# hib_main.net
KiCad netlist of a schematic drawn in EAGLE
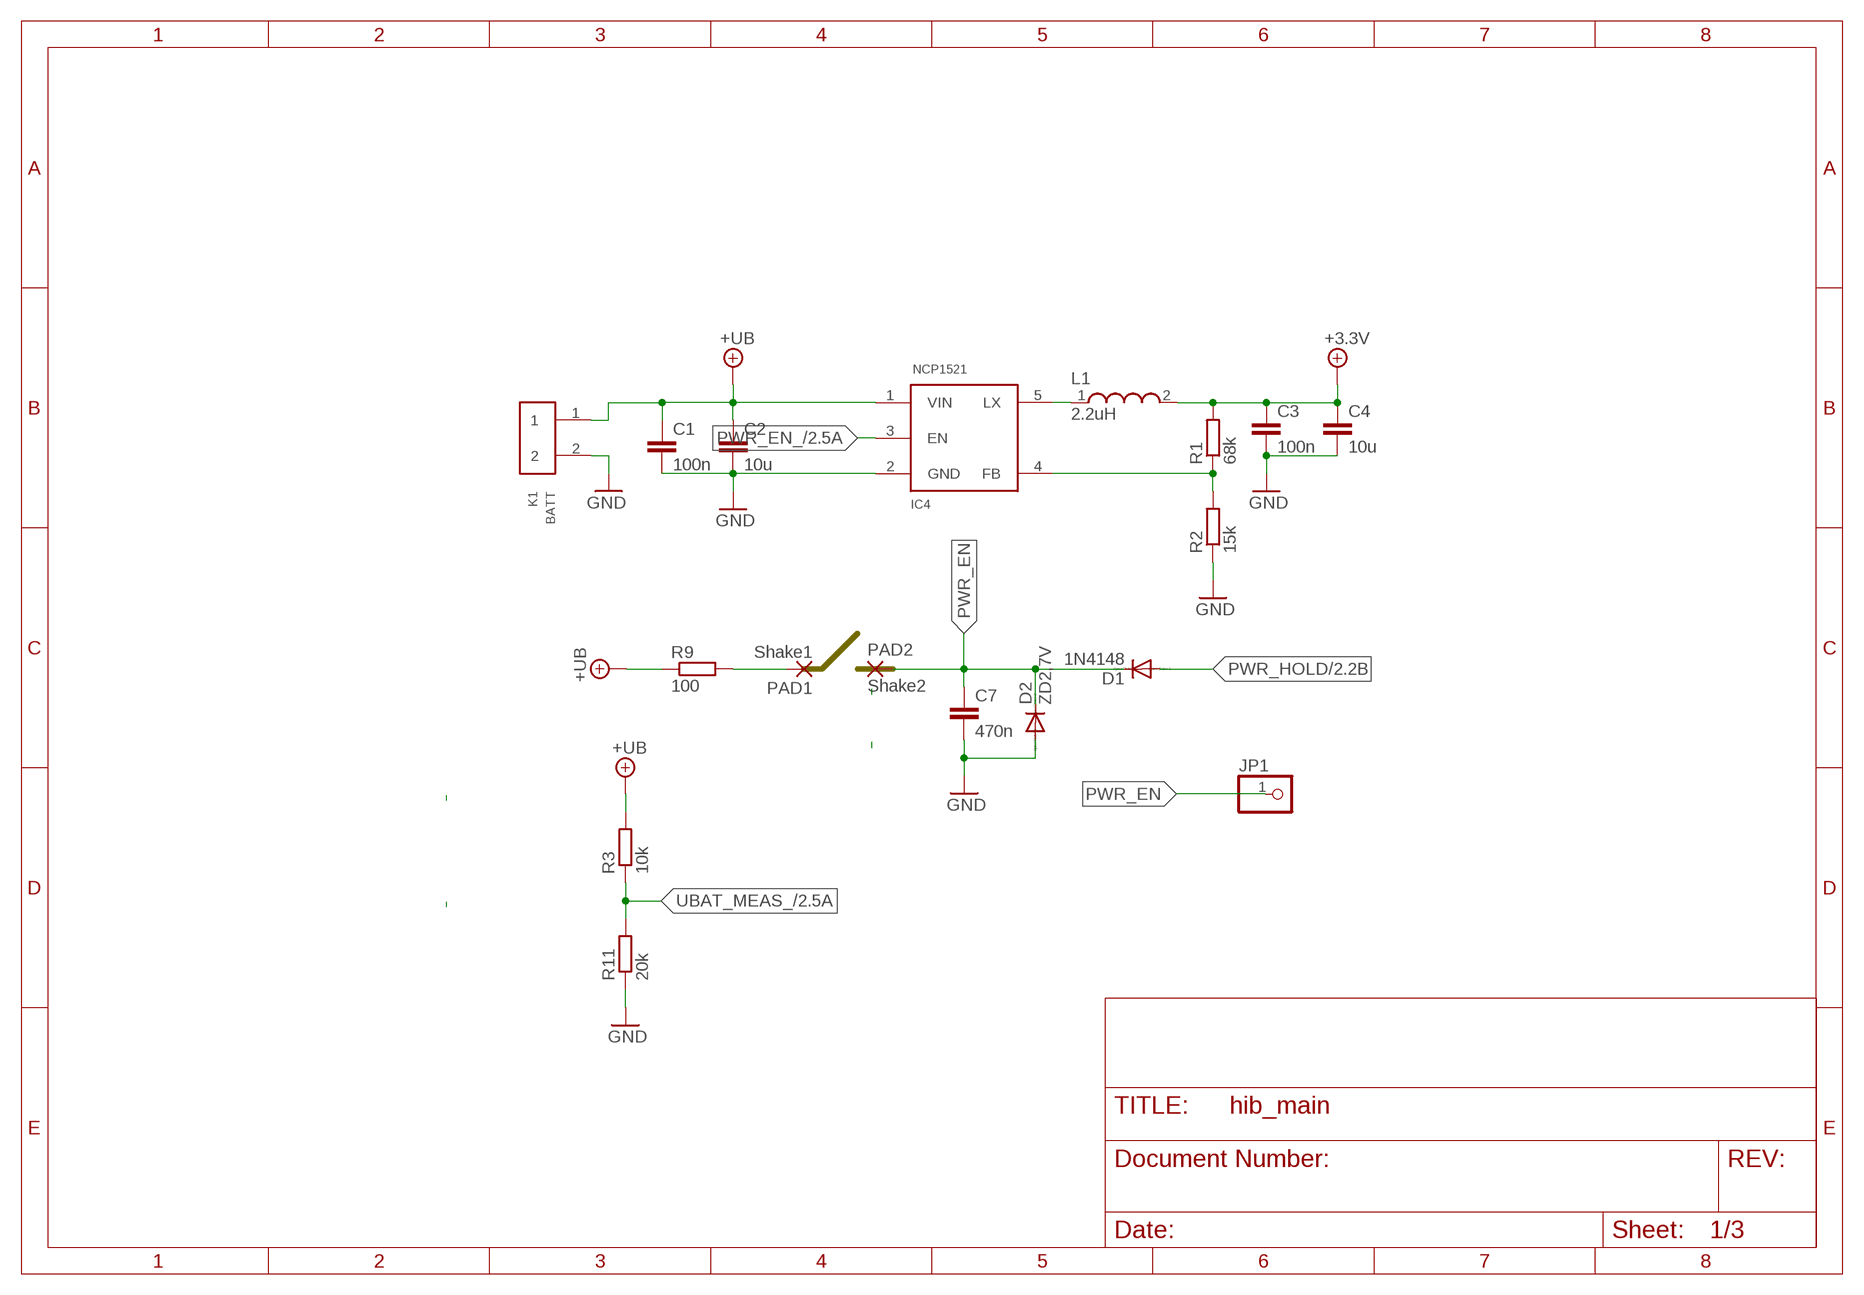
[diagram p0: schematic, sheet 1]
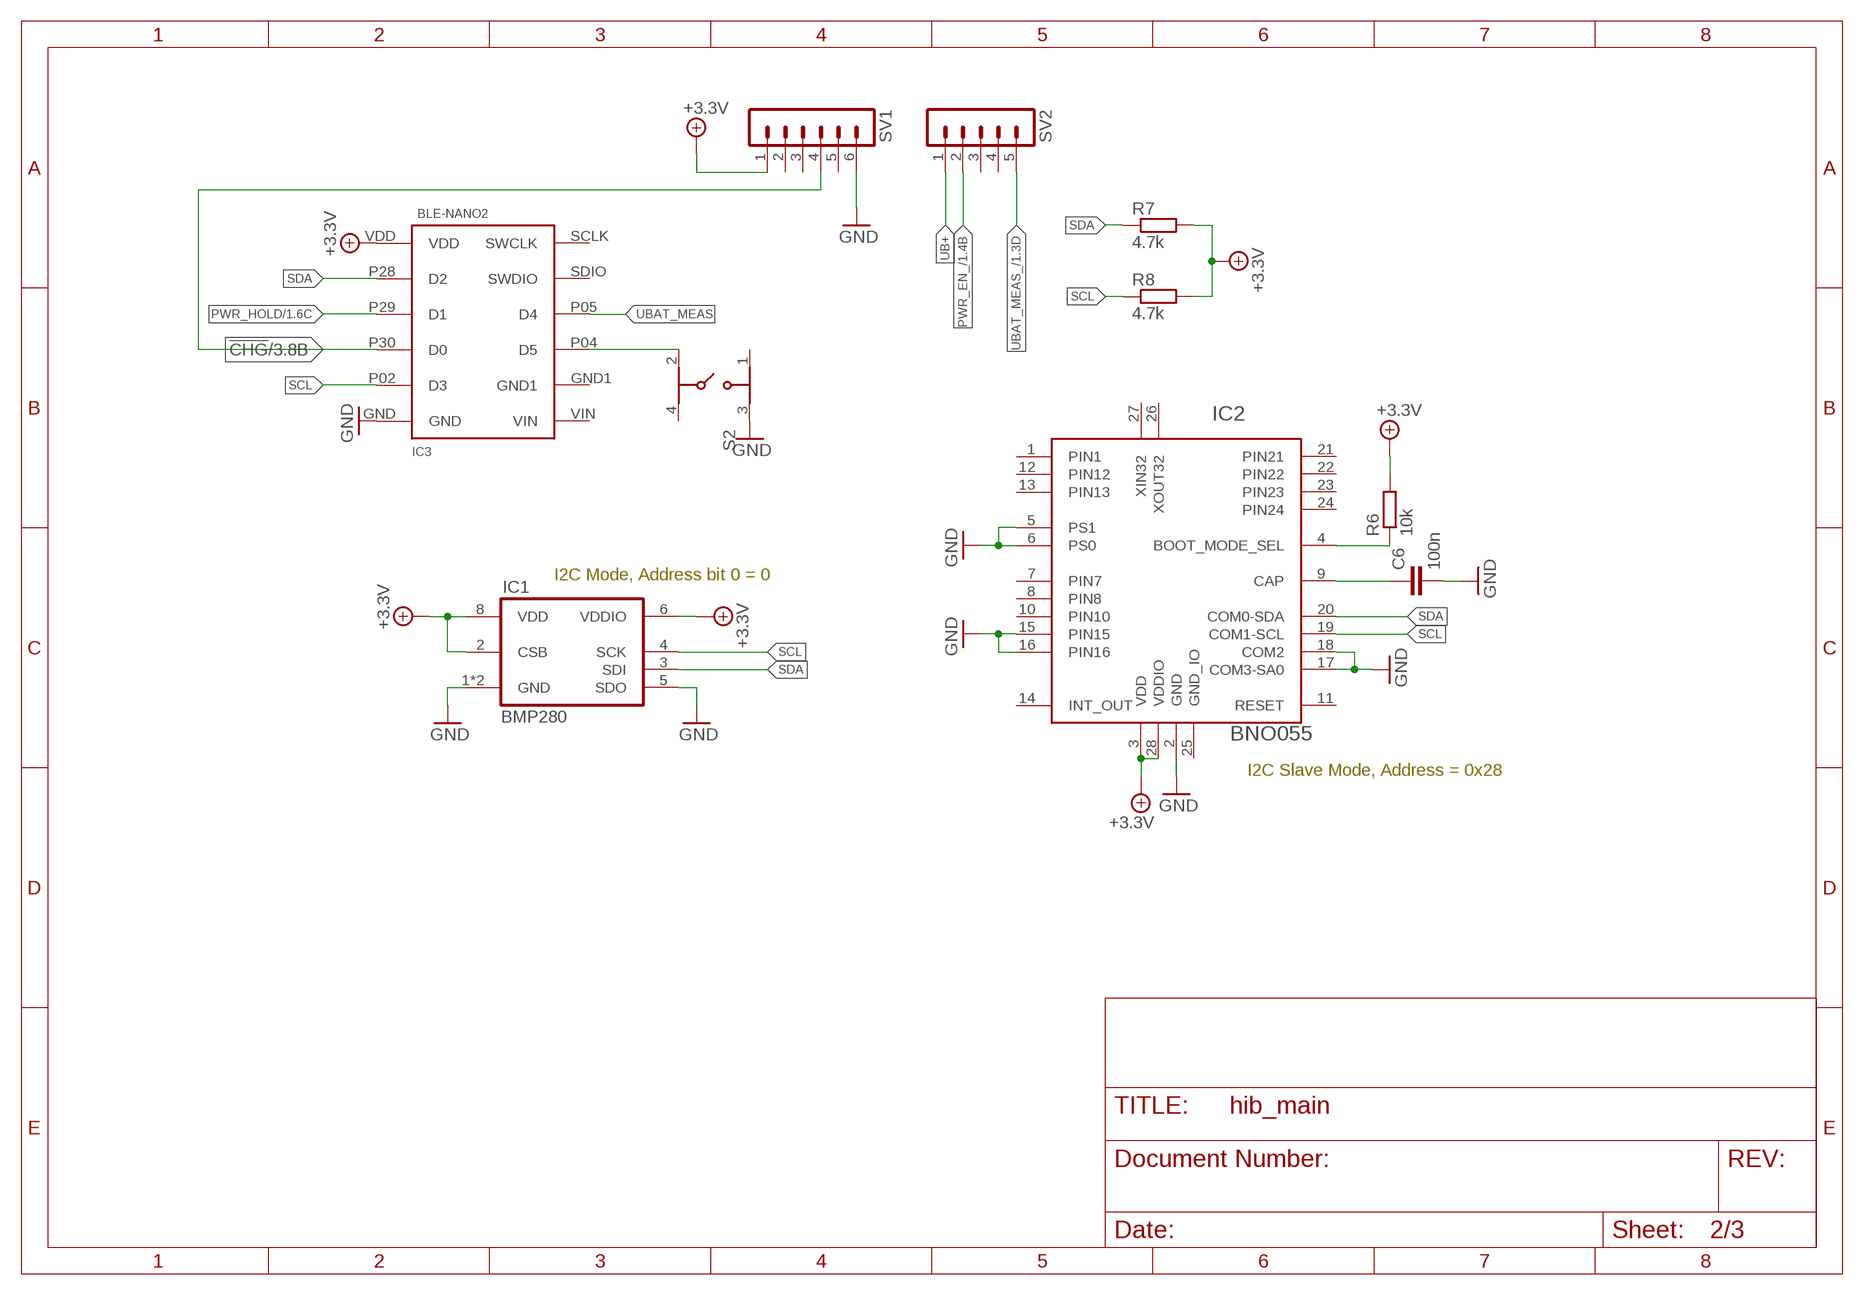
[diagram p1: schematic, sheet 2]
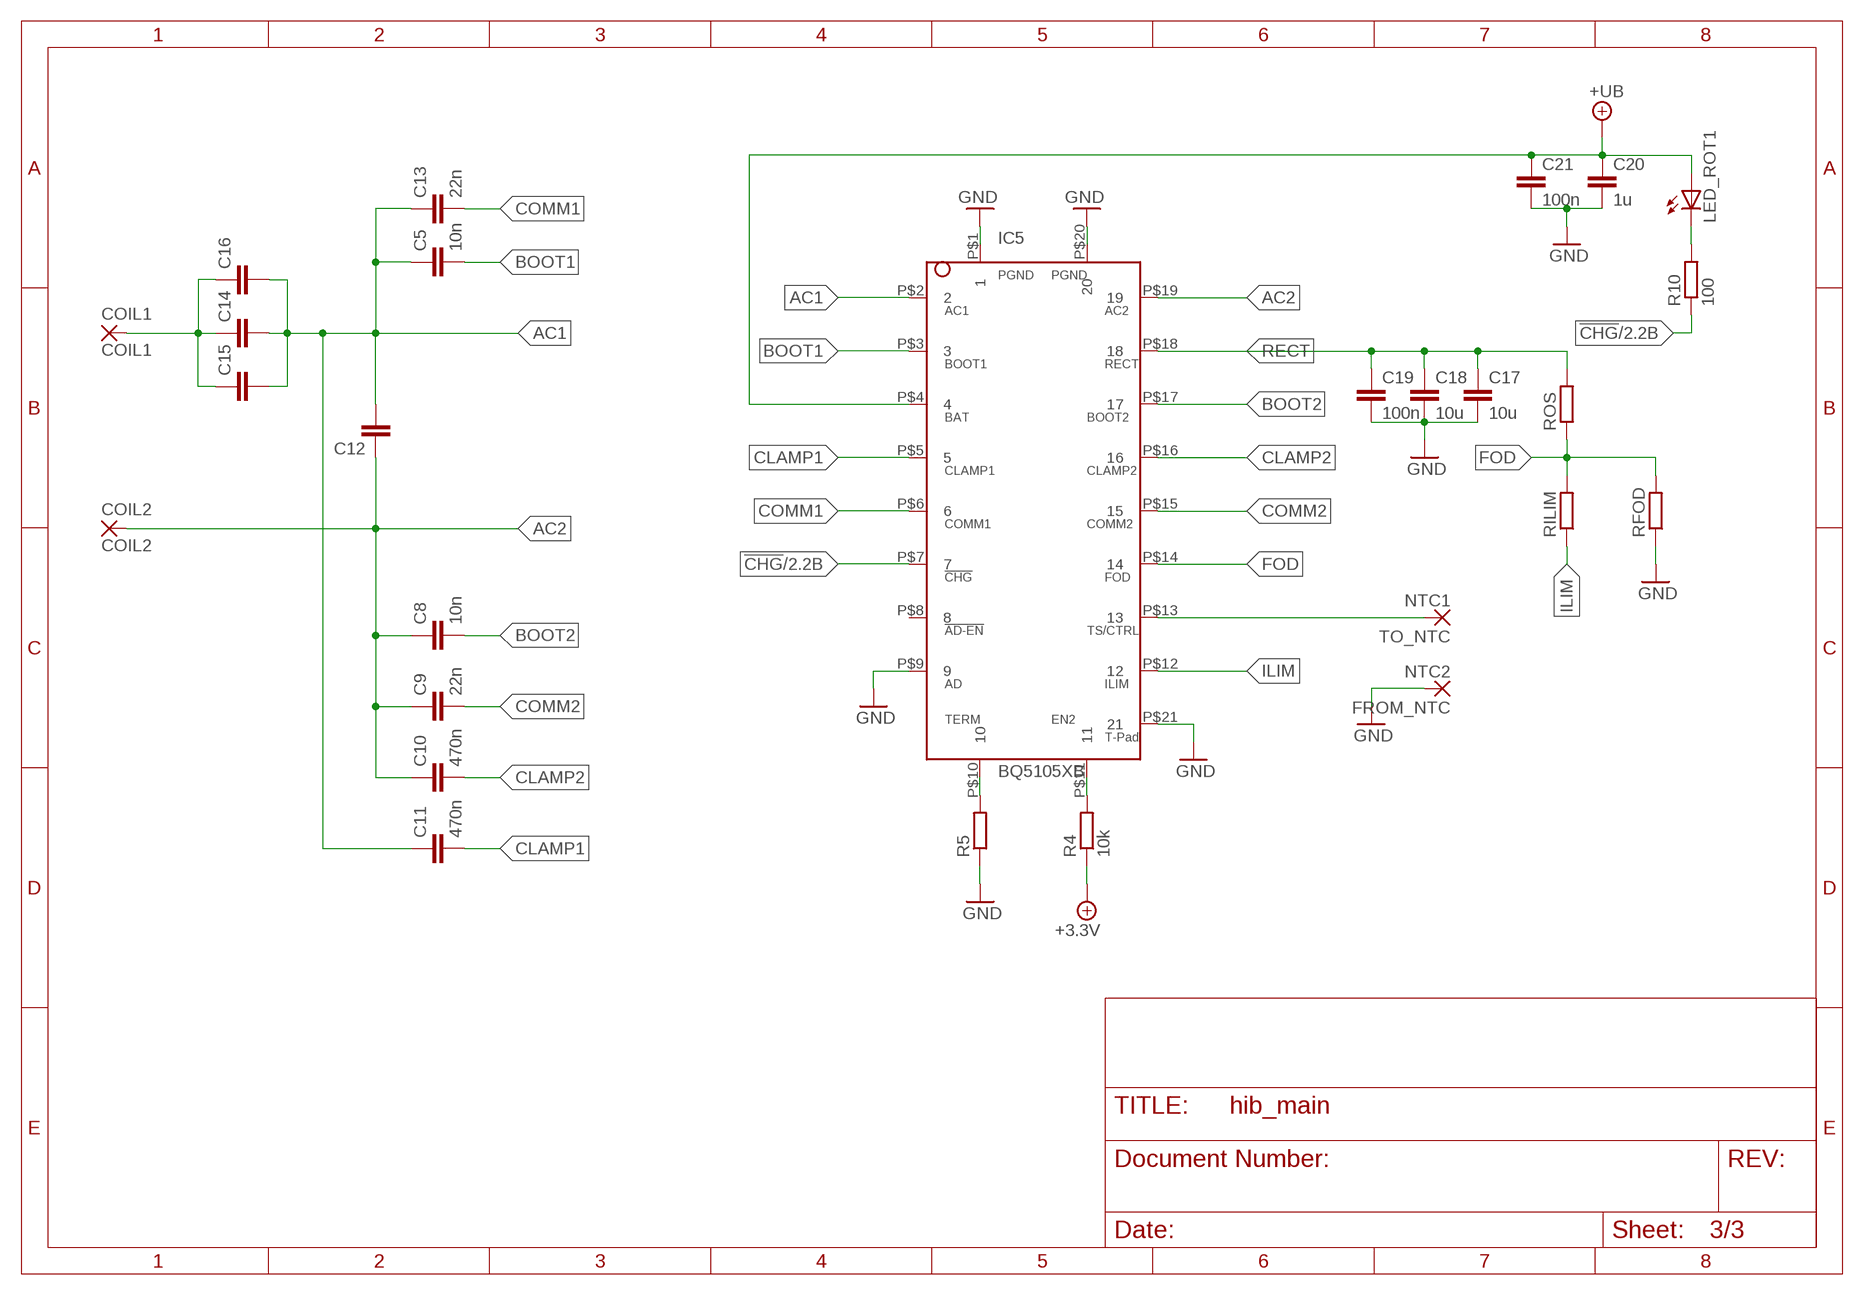
[diagram p2: schematic, sheet 3]

(export (version "E")
  (design (tool "Eeschema 10.0.6"))
  (components
    (comp (ref "C6")
      (value "100n")
      (footprint "eagle-import:C0805M")
      (libsource (lib "eagle-import") (part "C-EUC0805M"))
    )
    (comp (ref "IC1")
      (value "BMP280")
      (footprint "eagle-import:BMP280")
      (libsource (lib "eagle-import") (part "BMP280"))
    )
    (comp (ref "IC2")
      (value "BNO055")
      (footprint "eagle-import:LGA-28_3.80X5.20_0.5")
      (libsource (lib "eagle-import") (part "1658_BNO055"))
    )
    (comp (ref "IC3")
      (value "BLE-NANO2")
      (footprint "eagle-import:BLE-NANO2")
      (libsource (lib "eagle-import") (part "BLE-NANO2"))
    )
    (comp (ref "R6")
      (value "10k")
      (footprint "eagle-import:R0805M")
      (libsource (lib "eagle-import") (part "R-EU_R0805M"))
    )
    (comp (ref "R7")
      (value "4.7k")
      (footprint "eagle-import:R0805M")
      (libsource (lib "eagle-import") (part "R-EU_R0805M"))
    )
    (comp (ref "R8")
      (value "4.7k")
      (footprint "eagle-import:R0805M")
      (libsource (lib "eagle-import") (part "R-EU_R0805M"))
    )
    (comp (ref "S2")
      (value "434153017835")
      (footprint "eagle-import:434153017835")
      (libsource (lib "eagle-import") (part "434153017835"))
    )
    (comp (ref "SV1")
      (value "MA06-1")
      (footprint "eagle-import:MA06-1")
      (libsource (lib "eagle-import") (part "MA06-1"))
    )
    (comp (ref "SV2")
      (value "MA05-1")
      (footprint "eagle-import:MA05-1")
      (libsource (lib "eagle-import") (part "MA05-1"))
    )
    (comp (ref "C1")
      (value "100n")
      (footprint "eagle-import:C0805K")
      (libsource (lib "eagle-import") (part "rcl_334_C-EUC0805K"))
    )
    (comp (ref "C2")
      (value "10u")
      (footprint "eagle-import:C0805K")
      (libsource (lib "eagle-import") (part "rcl_334_C-EUC0805K"))
    )
    (comp (ref "C3")
      (value "100n")
      (footprint "eagle-import:C0805M")
      (libsource (lib "eagle-import") (part "C-EUC0805M"))
    )
    (comp (ref "C4")
      (value "10u")
      (footprint "eagle-import:C0805M")
      (libsource (lib "eagle-import") (part "C-EUC0805M"))
    )
    (comp (ref "C7")
      (value "470n")
      (footprint "eagle-import:C0805M")
      (libsource (lib "eagle-import") (part "C-EUC0805M"))
    )
    (comp (ref "D1")
      (value "1N4148")
      (footprint "eagle-import:MINIMELF")
      (libsource (lib "eagle-import") (part "DIODE-MINIMELF"))
    )
    (comp (ref "D2")
      (value "ZD2,7V")
      (footprint "eagle-import:MINIMELF")
      (libsource (lib "eagle-import") (part "DIODE-MINIMELF"))
    )
    (comp (ref "IC4")
      (value "NCP1521")
      (footprint "eagle-import:SOT23-5L")
      (libsource (lib "eagle-import") (part "NCP1521"))
    )
    (comp (ref "JP1")
      (value "PINHD-1X1")
      (footprint "eagle-import:1X01")
      (libsource (lib "eagle-import") (part "PINHD-1X1"))
    )
    (comp (ref "K1")
      (value "BATT")
      (footprint "eagle-import:620102131822")
      (libsource (lib "eagle-import") (part "620102131822"))
    )
    (comp (ref "L1")
      (value "2.2uH")
      (footprint "eagle-import:WE-MPSB_0805(W=4.0)")
      (libsource (lib "eagle-import") (part "WE-MPSB_0805(HC)"))
    )
    (comp (ref "PAD1")
      (value "Shake1")
      (footprint "eagle-import:SMD1,27-2,54")
      (libsource (lib "eagle-import") (part "WIREPADSMD1,27-254"))
    )
    (comp (ref "PAD2")
      (value "Shake2")
      (footprint "eagle-import:SMD1,27-2,54")
      (libsource (lib "eagle-import") (part "WIREPADSMD1,27-254"))
    )
    (comp (ref "R1")
      (value "68k")
      (footprint "eagle-import:R0603")
      (libsource (lib "eagle-import") (part "R-EU_R0603"))
    )
    (comp (ref "R2")
      (value "15k")
      (footprint "eagle-import:R0603")
      (libsource (lib "eagle-import") (part "R-EU_R0603"))
    )
    (comp (ref "R3")
      (value "10k")
      (footprint "eagle-import:R0603")
      (libsource (lib "eagle-import") (part "R-EU_R0603"))
    )
    (comp (ref "R9")
      (value "100")
      (footprint "eagle-import:R0603")
      (libsource (lib "eagle-import") (part "R-EU_R0603"))
    )
    (comp (ref "R11")
      (value "20k")
      (footprint "eagle-import:R0603")
      (libsource (lib "eagle-import") (part "R-EU_R0603"))
    )
    (comp (ref "C5")
      (value "10n")
      (footprint "eagle-import:C0603K")
      (libsource (lib "eagle-import") (part "rcl_334_C-EUC0603K"))
    )
    (comp (ref "C8")
      (value "10n")
      (footprint "eagle-import:C0603K")
      (libsource (lib "eagle-import") (part "rcl_334_C-EUC0603K"))
    )
    (comp (ref "C9")
      (value "22n")
      (footprint "eagle-import:C0603K")
      (libsource (lib "eagle-import") (part "rcl_334_C-EUC0603K"))
    )
    (comp (ref "C10")
      (value "470n")
      (footprint "eagle-import:C0603K")
      (libsource (lib "eagle-import") (part "rcl_334_C-EUC0603K"))
    )
    (comp (ref "C11")
      (value "470n")
      (footprint "eagle-import:C0603K")
      (libsource (lib "eagle-import") (part "rcl_334_C-EUC0603K"))
    )
    (comp (ref "C12")
      (value "C-EUC0603K")
      (footprint "eagle-import:C0603K")
      (libsource (lib "eagle-import") (part "rcl_334_C-EUC0603K"))
    )
    (comp (ref "C13")
      (value "22n")
      (footprint "eagle-import:C0603K")
      (libsource (lib "eagle-import") (part "rcl_334_C-EUC0603K"))
    )
    (comp (ref "C14")
      (value "C-EUC0603K")
      (footprint "eagle-import:C0603K")
      (libsource (lib "eagle-import") (part "rcl_334_C-EUC0603K"))
    )
    (comp (ref "C15")
      (value "C-EUC0603K")
      (footprint "eagle-import:C0603K")
      (libsource (lib "eagle-import") (part "rcl_334_C-EUC0603K"))
    )
    (comp (ref "C16")
      (value "C-EUC0603K")
      (footprint "eagle-import:C0603K")
      (libsource (lib "eagle-import") (part "rcl_334_C-EUC0603K"))
    )
    (comp (ref "C17")
      (value "10u")
      (footprint "eagle-import:C0603K")
      (libsource (lib "eagle-import") (part "rcl_334_C-EUC0603K"))
    )
    (comp (ref "C18")
      (value "10u")
      (footprint "eagle-import:C0603K")
      (libsource (lib "eagle-import") (part "rcl_334_C-EUC0603K"))
    )
    (comp (ref "C19")
      (value "100n")
      (footprint "eagle-import:C0603K")
      (libsource (lib "eagle-import") (part "rcl_334_C-EUC0603K"))
    )
    (comp (ref "C20")
      (value "1u")
      (footprint "eagle-import:C0603K")
      (libsource (lib "eagle-import") (part "rcl_334_C-EUC0603K"))
    )
    (comp (ref "C21")
      (value "100n")
      (footprint "eagle-import:C0603K")
      (libsource (lib "eagle-import") (part "rcl_334_C-EUC0603K"))
    )
    (comp (ref "COIL1")
      (value "COIL1")
      (footprint "eagle-import:SMD1,27-2,54")
      (libsource (lib "eagle-import") (part "wirepad_412_WIREPADSMD1,27-254"))
    )
    (comp (ref "COIL2")
      (value "COIL2")
      (footprint "eagle-import:SMD1,27-2,54")
      (libsource (lib "eagle-import") (part "wirepad_412_WIREPADSMD1,27-254"))
    )
    (comp (ref "FROM_NTC")
      (value "NTC2")
      (footprint "eagle-import:SMD1,27-2,54")
      (libsource (lib "eagle-import") (part "wirepad_412_WIREPADSMD1,27-254"))
    )
    (comp (ref "IC5")
      (value "BQ5105XB")
      (footprint "eagle-import:VQFN_BQ5105B")
      (libsource (lib "eagle-import") (part "BQ5105XB"))
    )
    (comp (ref "LED_ROT1")
      (value "LEDCHIP-LED0603")
      (footprint "eagle-import:CHIP-LED0603")
      (libsource (lib "eagle-import") (part "LEDCHIP-LED0603"))
    )
    (comp (ref "R4")
      (value "10k")
      (footprint "eagle-import:R0805")
      (libsource (lib "eagle-import") (part "rcl_334_R-EU_R0805"))
    )
    (comp (ref "R5")
      (value "R-EU_R0603")
      (footprint "eagle-import:R0603")
      (libsource (lib "eagle-import") (part "rcl_334_R-EU_R0603"))
    )
    (comp (ref "R10")
      (value "100")
      (footprint "eagle-import:R0603")
      (libsource (lib "eagle-import") (part "rcl_334_R-EU_R0603"))
    )
    (comp (ref "RFOD")
      (value "R-EU_R0805")
      (footprint "eagle-import:R0805")
      (libsource (lib "eagle-import") (part "rcl_334_R-EU_R0805"))
    )
    (comp (ref "RILIM")
      (value "R-EU_R0805")
      (footprint "eagle-import:R0805")
      (libsource (lib "eagle-import") (part "rcl_334_R-EU_R0805"))
    )
    (comp (ref "ROS")
      (value "R-EU_R0805")
      (footprint "eagle-import:R0805")
      (libsource (lib "eagle-import") (part "rcl_334_R-EU_R0805"))
    )
    (comp (ref "TO_NTC")
      (value "NTC1")
      (footprint "eagle-import:SMD1,27-2,54")
      (libsource (lib "eagle-import") (part "wirepad_412_WIREPADSMD1,27-254"))
    )
  )
  (nets
    (net (code "1") (name "+3,3V") (class "Default")
      (node (ref "C3") (pin "1") (pinfunction "1_1") (pintype "passive"))
      (node (ref "C4") (pin "1") (pinfunction "1_1") (pintype "passive"))
      (node (ref "IC1") (pin "2") (pinfunction "CSB_2") (pintype "input"))
      (node (ref "IC1") (pin "6") (pinfunction "VDDIO_6") (pintype "power_in"))
      (node (ref "IC1") (pin "8") (pinfunction "VDD_8") (pintype "power_in"))
      (node (ref "IC2") (pin "28") (pinfunction "VDDIO_28") (pintype "power_in"))
      (node (ref "IC2") (pin "3") (pinfunction "VDD_3") (pintype "power_in"))
      (node (ref "IC3") (pin "VDD") (pinfunction "VDD_VDD") (pintype "bidirectional"))
      (node (ref "L1") (pin "2") (pinfunction "2_2") (pintype "passive"))
      (node (ref "R1") (pin "2") (pinfunction "2_2") (pintype "passive"))
      (node (ref "R4") (pin "1") (pinfunction "1_1") (pintype "passive"))
      (node (ref "R6") (pin "2") (pinfunction "2_2") (pintype "passive"))
      (node (ref "R7") (pin "2") (pinfunction "2_2") (pintype "passive"))
      (node (ref "R8") (pin "2") (pinfunction "2_2") (pintype "passive"))
      (node (ref "SV1") (pin "1") (pinfunction "1_1") (pintype "passive"))
    )
    (net (code "2") (name "+UB") (class "Default")
      (node (ref "C1") (pin "1") (pinfunction "1_1") (pintype "passive"))
      (node (ref "C2") (pin "1") (pinfunction "1_1") (pintype "passive"))
      (node (ref "C20") (pin "1") (pinfunction "1_1") (pintype "passive"))
      (node (ref "C21") (pin "1") (pinfunction "1_1") (pintype "passive"))
      (node (ref "IC4") (pin "1") (pinfunction "VIN_1") (pintype "bidirectional"))
      (node (ref "IC5") (pin "P$4") (pinfunction "4_P$4") (pintype "bidirectional"))
      (node (ref "K1") (pin "1") (pinfunction "1_1") (pintype "passive"))
      (node (ref "LED_ROT1") (pin "A") (pinfunction "A_A") (pintype "passive"))
      (node (ref "R3") (pin "2") (pinfunction "2_2") (pintype "passive"))
      (node (ref "R9") (pin "1") (pinfunction "1_1") (pintype "passive"))
    )
    (net (code "3") (name "AC1") (class "Default")
      (node (ref "C11") (pin "1") (pinfunction "1_1") (pintype "passive"))
      (node (ref "C12") (pin "2") (pinfunction "2_2") (pintype "passive"))
      (node (ref "C13") (pin "1") (pinfunction "1_1") (pintype "passive"))
      (node (ref "C14") (pin "2") (pinfunction "2_2") (pintype "passive"))
      (node (ref "C15") (pin "2") (pinfunction "2_2") (pintype "passive"))
      (node (ref "C16") (pin "2") (pinfunction "2_2") (pintype "passive"))
      (node (ref "C5") (pin "1") (pinfunction "1_1") (pintype "passive"))
      (node (ref "IC5") (pin "P$2") (pinfunction "2_P$2") (pintype "bidirectional"))
    )
    (net (code "4") (name "AC2") (class "Default")
      (node (ref "C10") (pin "1") (pinfunction "1_1") (pintype "passive"))
      (node (ref "C12") (pin "1") (pinfunction "1_1") (pintype "passive"))
      (node (ref "C8") (pin "1") (pinfunction "1_1") (pintype "passive"))
      (node (ref "C9") (pin "1") (pinfunction "1_1") (pintype "passive"))
      (node (ref "COIL2") (pin "1") (pinfunction "P_1") (pintype "passive"))
      (node (ref "IC5") (pin "P$19") (pinfunction "19_P$19") (pintype "bidirectional"))
    )
    (net (code "5") (name "BOOT1") (class "Default")
      (node (ref "C5") (pin "2") (pinfunction "2_2") (pintype "passive"))
      (node (ref "IC5") (pin "P$3") (pinfunction "3_P$3") (pintype "bidirectional"))
    )
    (net (code "6") (name "BOOT2") (class "Default")
      (node (ref "C8") (pin "2") (pinfunction "2_2") (pintype "passive"))
      (node (ref "IC5") (pin "P$17") (pinfunction "17_P$17") (pintype "bidirectional"))
    )
    (net (code "7") (name "CLAMP1") (class "Default")
      (node (ref "C11") (pin "2") (pinfunction "2_2") (pintype "passive"))
      (node (ref "IC5") (pin "P$5") (pinfunction "5_P$5") (pintype "bidirectional"))
    )
    (net (code "8") (name "CLAMP2") (class "Default")
      (node (ref "C10") (pin "2") (pinfunction "2_2") (pintype "passive"))
      (node (ref "IC5") (pin "P$16") (pinfunction "16_P$16") (pintype "bidirectional"))
    )
    (net (code "9") (name "COMM1") (class "Default")
      (node (ref "C13") (pin "2") (pinfunction "2_2") (pintype "passive"))
      (node (ref "IC5") (pin "P$6") (pinfunction "6_P$6") (pintype "bidirectional"))
    )
    (net (code "10") (name "COMM2") (class "Default")
      (node (ref "C9") (pin "2") (pinfunction "2_2") (pintype "passive"))
      (node (ref "IC5") (pin "P$15") (pinfunction "15_P$15") (pintype "bidirectional"))
    )
    (net (code "11") (name "FOD") (class "Default")
      (node (ref "IC5") (pin "P$14") (pinfunction "14_P$14") (pintype "bidirectional"))
      (node (ref "RFOD") (pin "2") (pinfunction "2_2") (pintype "passive"))
      (node (ref "RILIM") (pin "2") (pinfunction "2_2") (pintype "passive"))
      (node (ref "ROS") (pin "1") (pinfunction "1_1") (pintype "passive"))
    )
    (net (code "12") (name "GND") (class "Default")
      (node (ref "C1") (pin "2") (pinfunction "2_2") (pintype "passive"))
      (node (ref "C17") (pin "2") (pinfunction "2_2") (pintype "passive"))
      (node (ref "C18") (pin "2") (pinfunction "2_2") (pintype "passive"))
      (node (ref "C19") (pin "2") (pinfunction "2_2") (pintype "passive"))
      (node (ref "C2") (pin "2") (pinfunction "2_2") (pintype "passive"))
      (node (ref "C20") (pin "2") (pinfunction "2_2") (pintype "passive"))
      (node (ref "C21") (pin "2") (pinfunction "2_2") (pintype "passive"))
      (node (ref "C3") (pin "2") (pinfunction "2_2") (pintype "passive"))
      (node (ref "C4") (pin "2") (pinfunction "2_2") (pintype "passive"))
      (node (ref "C6") (pin "2") (pinfunction "2_2") (pintype "passive"))
      (node (ref "C7") (pin "2") (pinfunction "2_2") (pintype "passive"))
      (node (ref "D2") (pin "A") (pinfunction "A_A") (pintype "passive"))
      (node (ref "FROM_NTC") (pin "1") (pinfunction "P_1") (pintype "passive"))
      (node (ref "IC1") (pin "1") (pinfunction "GND_1") (pintype "power_in"))
      (node (ref "IC1") (pin "5") (pinfunction "SDO_5") (pintype "input"))
      (node (ref "IC1") (pin "7") (pinfunction "GND_7") (pintype "power_in"))
      (node (ref "IC2") (pin "15") (pinfunction "PIN15_15") (pintype "passive"))
      (node (ref "IC2") (pin "16") (pinfunction "PIN16_16") (pintype "passive"))
      (node (ref "IC2") (pin "17") (pinfunction "COM3-SA0_17") (pintype "bidirectional"))
      (node (ref "IC2") (pin "18") (pinfunction "COM2_18") (pintype "bidirectional"))
      (node (ref "IC2") (pin "2") (pinfunction "GND_2") (pintype "power_in"))
      (node (ref "IC2") (pin "5") (pinfunction "PS1_5") (pintype "input"))
      (node (ref "IC2") (pin "6") (pinfunction "PS0_6") (pintype "input"))
      (node (ref "IC3") (pin "GND") (pinfunction "GND_GND") (pintype "bidirectional"))
      (node (ref "IC4") (pin "2") (pinfunction "GND_2") (pintype "bidirectional"))
      (node (ref "IC5") (pin "P$1") (pinfunction "1_P$1") (pintype "bidirectional"))
      (node (ref "IC5") (pin "P$20") (pinfunction "20_P$20") (pintype "bidirectional"))
      (node (ref "IC5") (pin "P$21") (pinfunction "21_P$21") (pintype "bidirectional"))
      (node (ref "IC5") (pin "P$9") (pinfunction "9_P$9") (pintype "bidirectional"))
      (node (ref "K1") (pin "2") (pinfunction "2_2") (pintype "passive"))
      (node (ref "R11") (pin "1") (pinfunction "1_1") (pintype "passive"))
      (node (ref "R2") (pin "1") (pinfunction "1_1") (pintype "passive"))
      (node (ref "R5") (pin "1") (pinfunction "1_1") (pintype "passive"))
      (node (ref "RFOD") (pin "1") (pinfunction "1_1") (pintype "passive"))
      (node (ref "S2") (pin "3") (pinfunction "2_3") (pintype "passive"))
      (node (ref "SV1") (pin "6") (pinfunction "6_6") (pintype "passive"))
    )
    (net (code "13") (name "GND_IO") (class "Default")
      (node (ref "IC2") (pin "25") (pinfunction "GND_IO_25") (pintype "power_in"))
    )
    (net (code "14") (name "ILIM") (class "Default")
      (node (ref "IC5") (pin "P$12") (pinfunction "12_P$12") (pintype "bidirectional"))
      (node (ref "RILIM") (pin "1") (pinfunction "1_1") (pintype "passive"))
    )
    (net (code "15") (name "Net-(COIL1-P)") (class "Default")
      (node (ref "C14") (pin "1") (pinfunction "1_1") (pintype "passive"))
      (node (ref "C15") (pin "1") (pinfunction "1_1") (pintype "passive"))
      (node (ref "C16") (pin "1") (pinfunction "1_1") (pintype "passive"))
      (node (ref "COIL1") (pin "1") (pinfunction "P_1") (pintype "passive"))
    )
    (net (code "16") (name "Net-(IC2-BOOT_MODE_SEL)") (class "Default")
      (node (ref "IC2") (pin "4") (pinfunction "BOOT_MODE_SEL_4") (pintype "input"))
      (node (ref "R6") (pin "1") (pinfunction "1_1") (pintype "passive"))
    )
    (net (code "17") (name "Net-(IC2-CAP)") (class "Default")
      (node (ref "C6") (pin "1") (pinfunction "1_1") (pintype "passive"))
      (node (ref "IC2") (pin "9") (pinfunction "CAP_9") (pintype "tri_state"))
    )
    (net (code "18") (name "Net-(IC3-D5)") (class "Default")
      (node (ref "IC3") (pin "P04") (pinfunction "D5_P04") (pintype "bidirectional"))
      (node (ref "S2") (pin "2") (pinfunction "3_2") (pintype "passive"))
    )
    (net (code "19") (name "Net-(IC4-FB)") (class "Default")
      (node (ref "IC4") (pin "4") (pinfunction "FB_4") (pintype "bidirectional"))
      (node (ref "R1") (pin "1") (pinfunction "1_1") (pintype "passive"))
      (node (ref "R2") (pin "2") (pinfunction "2_2") (pintype "passive"))
    )
    (net (code "20") (name "Net-(IC4-LX)") (class "Default")
      (node (ref "IC4") (pin "5") (pinfunction "LX_5") (pintype "bidirectional"))
      (node (ref "L1") (pin "1") (pinfunction "1_1") (pintype "passive"))
    )
    (net (code "21") (name "Net-(IC5-10)") (class "Default")
      (node (ref "IC5") (pin "P$10") (pinfunction "10_P$10") (pintype "bidirectional"))
      (node (ref "R5") (pin "2") (pinfunction "2_2") (pintype "passive"))
    )
    (net (code "22") (name "Net-(IC5-11)") (class "Default")
      (node (ref "IC5") (pin "P$11") (pinfunction "11_P$11") (pintype "bidirectional"))
      (node (ref "R4") (pin "2") (pinfunction "2_2") (pintype "passive"))
    )
    (net (code "23") (name "Net-(IC5-13)") (class "Default")
      (node (ref "IC5") (pin "P$13") (pinfunction "13_P$13") (pintype "bidirectional"))
      (node (ref "TO_NTC") (pin "1") (pinfunction "P_1") (pintype "passive"))
    )
    (net (code "24") (name "Net-(LED_ROT1-PadC)") (class "Default")
      (node (ref "LED_ROT1") (pin "C") (pinfunction "C_C") (pintype "passive"))
      (node (ref "R10") (pin "2") (pinfunction "2_2") (pintype "passive"))
    )
    (net (code "25") (name "Net-(PAD1-P)") (class "Default")
      (node (ref "PAD1") (pin "1") (pinfunction "P_1") (pintype "passive"))
      (node (ref "R9") (pin "2") (pinfunction "2_2") (pintype "passive"))
    )
    (net (code "26") (name "PWR_EN") (class "Default")
      (node (ref "C7") (pin "1") (pinfunction "1_1") (pintype "passive"))
      (node (ref "D1") (pin "C") (pinfunction "C_C") (pintype "passive"))
      (node (ref "D2") (pin "C") (pinfunction "C_C") (pintype "passive"))
      (node (ref "JP1") (pin "1") (pinfunction "1_1") (pintype "passive"))
      (node (ref "PAD2") (pin "1") (pinfunction "P_1") (pintype "passive"))
    )
    (net (code "27") (name "PWR_EN_") (class "Default")
      (node (ref "IC4") (pin "3") (pinfunction "EN_3") (pintype "bidirectional"))
      (node (ref "SV2") (pin "2") (pinfunction "2_2") (pintype "passive"))
    )
    (net (code "28") (name "PWR_HOLD") (class "Default")
      (node (ref "D1") (pin "A") (pinfunction "A_A") (pintype "passive"))
      (node (ref "IC3") (pin "P29") (pinfunction "D1_P29") (pintype "bidirectional"))
    )
    (net (code "29") (name "RECT") (class "Default")
      (node (ref "C17") (pin "1") (pinfunction "1_1") (pintype "passive"))
      (node (ref "C18") (pin "1") (pinfunction "1_1") (pintype "passive"))
      (node (ref "C19") (pin "1") (pinfunction "1_1") (pintype "passive"))
      (node (ref "IC5") (pin "P$18") (pinfunction "18_P$18") (pintype "bidirectional"))
      (node (ref "ROS") (pin "2") (pinfunction "2_2") (pintype "passive"))
    )
    (net (code "30") (name "SCL") (class "Default")
      (node (ref "IC1") (pin "4") (pinfunction "SCK_4") (pintype "bidirectional"))
      (node (ref "IC2") (pin "19") (pinfunction "COM1-SCL_19") (pintype "bidirectional"))
      (node (ref "IC3") (pin "P02") (pinfunction "D3_P02") (pintype "bidirectional"))
      (node (ref "R8") (pin "1") (pinfunction "1_1") (pintype "passive"))
    )
    (net (code "31") (name "SDA") (class "Default")
      (node (ref "IC1") (pin "3") (pinfunction "SDI_3") (pintype "bidirectional"))
      (node (ref "IC2") (pin "20") (pinfunction "COM0-SDA_20") (pintype "bidirectional"))
      (node (ref "IC3") (pin "P28") (pinfunction "D2_P28") (pintype "bidirectional"))
      (node (ref "R7") (pin "1") (pinfunction "1_1") (pintype "passive"))
    )
    (net (code "32") (name "UB+") (class "Default")
      (node (ref "SV2") (pin "1") (pinfunction "1_1") (pintype "passive"))
    )
    (net (code "33") (name "UBAT_MEAS") (class "Default")
      (node (ref "IC3") (pin "P05") (pinfunction "D4_P05") (pintype "bidirectional"))
    )
    (net (code "34") (name "UBAT_MEAS_") (class "Default")
      (node (ref "R11") (pin "2") (pinfunction "2_2") (pintype "passive"))
      (node (ref "R3") (pin "1") (pinfunction "1_1") (pintype "passive"))
      (node (ref "SV2") (pin "5") (pinfunction "5_5") (pintype "passive"))
    )
    (net (code "35") (name "unconnected-(IC2-INT_OUT-Pad14)") (class "Default")
      (node (ref "IC2") (pin "14") (pinfunction "INT_OUT_14") (pintype "output"))
    )
    (net (code "36") (name "unconnected-(IC2-PIN1-Pad1)") (class "Default")
      (node (ref "IC2") (pin "1") (pinfunction "PIN1_1") (pintype "no_connect"))
    )
    (net (code "37") (name "unconnected-(IC2-PIN7-Pad7)") (class "Default")
      (node (ref "IC2") (pin "7") (pinfunction "PIN7_7") (pintype "tri_state"))
    )
    (net (code "38") (name "unconnected-(IC2-PIN8-Pad8)") (class "Default")
      (node (ref "IC2") (pin "8") (pinfunction "PIN8_8") (pintype "tri_state"))
    )
    (net (code "39") (name "unconnected-(IC2-PIN10-Pad10)") (class "Default")
      (node (ref "IC2") (pin "10") (pinfunction "PIN10_10") (pintype "passive"))
    )
    (net (code "40") (name "unconnected-(IC2-PIN12-Pad12)") (class "Default")
      (node (ref "IC2") (pin "12") (pinfunction "PIN12_12") (pintype "passive"))
    )
    (net (code "41") (name "unconnected-(IC2-PIN13-Pad13)") (class "Default")
      (node (ref "IC2") (pin "13") (pinfunction "PIN13_13") (pintype "passive"))
    )
    (net (code "42") (name "unconnected-(IC2-PIN21-Pad21)") (class "Default")
      (node (ref "IC2") (pin "21") (pinfunction "PIN21_21") (pintype "passive"))
    )
    (net (code "43") (name "unconnected-(IC2-PIN22-Pad22)") (class "Default")
      (node (ref "IC2") (pin "22") (pinfunction "PIN22_22") (pintype "passive"))
    )
    (net (code "44") (name "unconnected-(IC2-PIN23-Pad23)") (class "Default")
      (node (ref "IC2") (pin "23") (pinfunction "PIN23_23") (pintype "passive"))
    )
    (net (code "45") (name "unconnected-(IC2-PIN24-Pad24)") (class "Default")
      (node (ref "IC2") (pin "24") (pinfunction "PIN24_24") (pintype "passive"))
    )
    (net (code "46") (name "unconnected-(IC2-RESET-Pad11)") (class "Default")
      (node (ref "IC2") (pin "11") (pinfunction "RESET_11") (pintype "input"))
    )
    (net (code "47") (name "unconnected-(IC2-XIN32-Pad27)") (class "Default")
      (node (ref "IC2") (pin "27") (pinfunction "XIN32_27") (pintype "bidirectional"))
    )
    (net (code "48") (name "unconnected-(IC2-XOUT32-Pad26)") (class "Default")
      (node (ref "IC2") (pin "26") (pinfunction "XOUT32_26") (pintype "output"))
    )
    (net (code "49") (name "unconnected-(IC3-PadGND1)") (class "Default")
      (node (ref "IC3") (pin "GND1") (pinfunction "GND1_GND1") (pintype "bidirectional"))
    )
    (net (code "50") (name "unconnected-(IC3-PadVIN)") (class "Default")
      (node (ref "IC3") (pin "VIN") (pinfunction "VIN_VIN") (pintype "bidirectional"))
    )
    (net (code "51") (name "unconnected-(IC3-SWCLK-PadSCLK)") (class "Default")
      (node (ref "IC3") (pin "SCLK") (pinfunction "SWCLK_SCLK") (pintype "bidirectional"))
    )
    (net (code "52") (name "unconnected-(IC3-SWDIO-PadSDIO)") (class "Default")
      (node (ref "IC3") (pin "SDIO") (pinfunction "SWDIO_SDIO") (pintype "bidirectional"))
    )
    (net (code "53") (name "unconnected-(IC5-8-PadP$8)") (class "Default")
      (node (ref "IC5") (pin "P$8") (pinfunction "8_P$8") (pintype "bidirectional"))
    )
    (net (code "54") (name "unconnected-(S2-Pad1)") (class "Default")
      (node (ref "S2") (pin "1") (pinfunction "1_1") (pintype "passive"))
    )
    (net (code "55") (name "unconnected-(S2-Pad4)") (class "Default")
      (node (ref "S2") (pin "4") (pinfunction "4_4") (pintype "passive"))
    )
    (net (code "56") (name "unconnected-(SV1-Pad2)") (class "Default")
      (node (ref "SV1") (pin "2") (pinfunction "2_2") (pintype "passive"))
    )
    (net (code "57") (name "unconnected-(SV1-Pad3)") (class "Default")
      (node (ref "SV1") (pin "3") (pinfunction "3_3") (pintype "passive"))
    )
    (net (code "58") (name "unconnected-(SV1-Pad5)") (class "Default")
      (node (ref "SV1") (pin "5") (pinfunction "5_5") (pintype "passive"))
    )
    (net (code "59") (name "unconnected-(SV2-Pad3)") (class "Default")
      (node (ref "SV2") (pin "3") (pinfunction "3_3") (pintype "passive"))
    )
    (net (code "60") (name "unconnected-(SV2-Pad4)") (class "Default")
      (node (ref "SV2") (pin "4") (pinfunction "4_4") (pintype "passive"))
    )
    (net (code "61") (name "~{CHG}") (class "Default")
      (node (ref "IC3") (pin "P30") (pinfunction "D0_P30") (pintype "bidirectional"))
      (node (ref "IC5") (pin "P$7") (pinfunction "7_P$7") (pintype "bidirectional"))
      (node (ref "R10") (pin "1") (pinfunction "1_1") (pintype "passive"))
      (node (ref "SV1") (pin "4") (pinfunction "4_4") (pintype "passive"))
    )
  )
)
